# Test.net
KiCad netlist of a schematic drawn in EasyEDA Pro
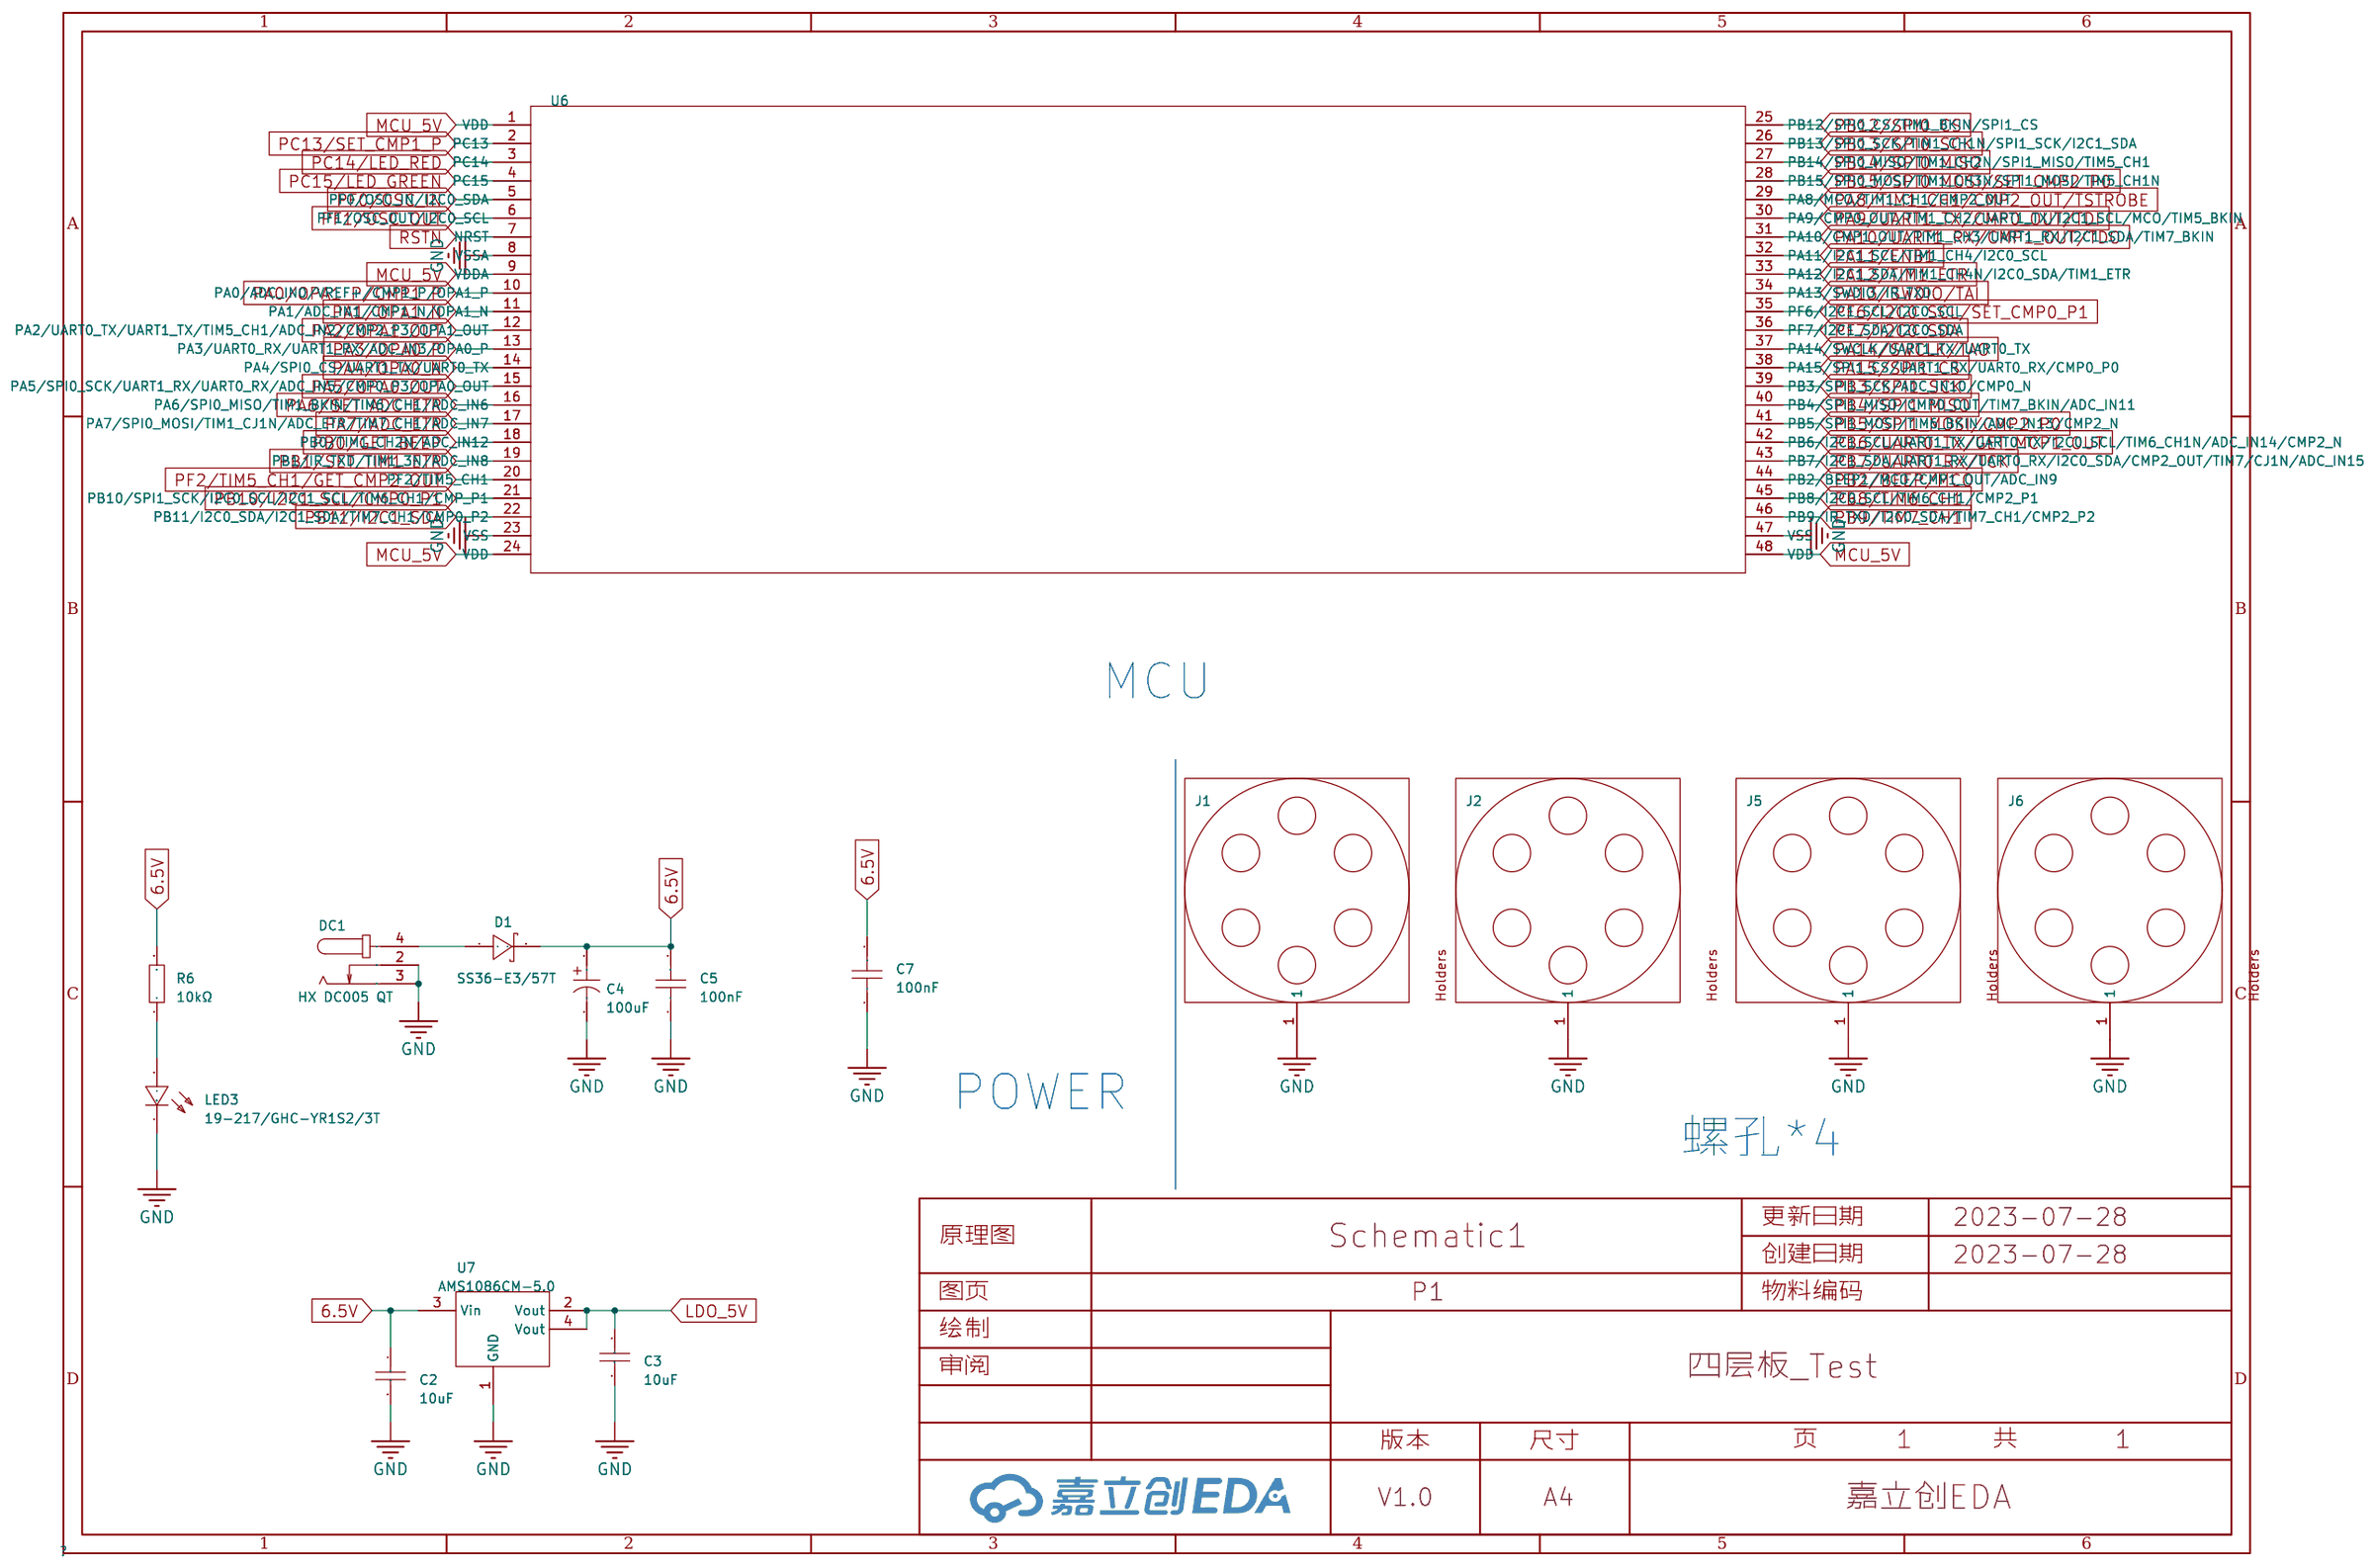
[diagram p0: schematic sheet]

(export (version "E")
  (design (tool "Eeschema 10.0.6"))
  (components
    (comp (ref "C2")
      (value "10uF")
      (footprint "easyedapro:C1206")
      (description "容值:10uF;精度:±10%;额定电压:50V;材质(温度系数):X5R;")
      (fields
        (field (name "Manufacturer Part") "CL31A106KBHNNNE")
        (field (name "Manufacturer") "SAMSUNG(三星)")
      )
      (libsource (lib "easyedapro") (part "CL31A106KBHNNNE"))
    )
    (comp (ref "C3")
      (value "10uF")
      (footprint "easyedapro:C1206")
      (description "容值:10uF;精度:±10%;额定电压:50V;材质(温度系数):X5R;")
      (fields
        (field (name "Manufacturer Part") "CL31A106KBHNNNE")
        (field (name "Manufacturer") "SAMSUNG(三星)")
      )
      (libsource (lib "easyedapro") (part "CL31A106KBHNNNE"))
    )
    (comp (ref "C4")
      (value "100uF")
      (footprint "easyedapro:CAP-SMD_BD6.3-L6.6-W6.6-LS7.6-FD-1")
      (description "容值:100uF;额定电压:35V;电容体直径:-;电容体长度:-;纹波电流:-;等效串联电阻:-;工作寿命:-;")
      (fields
        (field (name "Manufacturer Part") "RVE100UF35V67RV0072")
        (field (name "Manufacturer") "KNSCHA(科尼盛)")
      )
      (libsource (lib "easyedapro") (part "RVE100UF35V67RV0072"))
    )
    (comp (ref "C5")
      (value "100nF")
      (footprint "easyedapro:C0603")
      (description "容值:100nF;精度:±10%;额定电压:50V;材质(温度系数):X7R;")
      (fields
        (field (name "Manufacturer Part") "CL10B104KB8NNNC")
        (field (name "Manufacturer") "SAMSUNG(三星)")
      )
      (libsource (lib "easyedapro") (part "CL10B104KB8NNNC"))
    )
    (comp (ref "C7")
      (value "100nF")
      (footprint "easyedapro:C0603")
      (description "容值:100nF;精度:±10%;额定电压:50V;材质(温度系数):X7R;")
      (fields
        (field (name "Manufacturer Part") "CL10B104KB8NNNC")
        (field (name "Manufacturer") "SAMSUNG(三星)")
      )
      (libsource (lib "easyedapro") (part "CL10B104KB8NNNC"))
    )
    (comp (ref "D1")
      (value "SS36-E3/57T")
      (footprint "easyedapro:SMC_L7.1-W6.2-LS8.1-R-RD")
      (description "直流反向耐压（Vr）:60V;平均整流电流（Io）:3A;正向压降（Vf）:750mV @ 3A;")
      (fields (field (name "Manufacturer") "VISHAY(威世)"))
      (libsource (lib "easyedapro") (part "SS36-E3/57T"))
    )
    (comp (ref "DC1")
      (value "HX DC005 QT")
      (footprint "easyedapro:DC-IN-TH_HANXIA_HX-DC005-QT")
      (description "连接器类型:DC插座;安装方式:卧插;额定电流:1A;额定电压:12V;工作温度范围:-25°C~+85°C;")
      (fields (field (name "Manufacturer") "hanxia(韩下)"))
      (libsource (lib "easyedapro") (part "HX DC005 QT"))
    )
    (comp (ref "J1")
      (value "~")
      (footprint "easyedapro:DEMO板安装孔")
      (libsource (lib "easyedapro") (part "螺孔_3.1X6MM"))
    )
    (comp (ref "J2")
      (value "~")
      (footprint "easyedapro:DEMO板安装孔")
      (libsource (lib "easyedapro") (part "螺孔_3.1X6MM"))
    )
    (comp (ref "J5")
      (value "~")
      (footprint "easyedapro:DEMO板安装孔")
      (libsource (lib "easyedapro") (part "螺孔_3.1X6MM"))
    )
    (comp (ref "J6")
      (value "~")
      (footprint "easyedapro:DEMO板安装孔")
      (libsource (lib "easyedapro") (part "螺孔_3.1X6MM"))
    )
    (comp (ref "LED3")
      (value "19-217/GHC-YR1S2/3T")
      (footprint "easyedapro:LED0603-RD")
      (fields (field (name "Manufacturer") "EVERLIGHT(亿光)"))
      (libsource (lib "easyedapro") (part "19-217/GHC-YR1S2/3T"))
    )
    (comp (ref "R6")
      (value "10kΩ")
      (footprint "easyedapro:R0603")
      (description "电阻类型:厚膜电阻;阻值:10kΩ;精度:±1%;功率:100mW;温度系数:±100ppm/°C;最大工作电压:75V;工作温度范围:-55°C~+155°C;")
      (fields
        (field (name "Manufacturer Part") "0603WAF1002T5E")
        (field (name "Manufacturer") "UNI-ROYAL(厚声)")
      )
      (libsource (lib "easyedapro") (part "0603WAF1002T5E"))
    )
    (comp (ref "U6") (value "PT32A030C8T7") (libsource (lib "easyedapro") (part "PT32A030C8T7")))
    (comp (ref "U7")
      (value "AMS1086CM-5.0")
      (footprint "easyedapro:TO-263-3_L8.6-W10.2-P2.54-LS14.4-TL")
      (description "输出类型:固定;输出极性:正;最大输入电压:15V;输出电压:5V;输出电流:1.5A;电源纹波抑制比(PSRR):68dB@(120Hz);")
      (fields (field (name "Manufacturer") "AMS"))
      (libsource (lib "easyedapro") (part "AMS1086CM-5.0"))
    )
  )
  (nets
    (net (code "1") (name "6.5V") (class "Default")
      (node (ref "C2") (pin "1") (pinfunction "1_1") (pintype "input"))
      (node (ref "C4") (pin "1") (pinfunction "1_1") (pintype "input"))
      (node (ref "C5") (pin "2") (pinfunction "2_2") (pintype "input"))
      (node (ref "C7") (pin "2") (pinfunction "2_2") (pintype "input"))
      (node (ref "D1") (pin "2") (pinfunction "K_2") (pintype "input"))
      (node (ref "R6") (pin "2") (pinfunction "2_2") (pintype "input"))
      (node (ref "U7") (pin "3") (pinfunction "Vin_3") (pintype "input"))
    )
    (net (code "2") (name "GND") (class "Default")
      (node (ref "C2") (pin "2") (pinfunction "2_2") (pintype "input"))
      (node (ref "C3") (pin "1") (pinfunction "1_1") (pintype "input"))
      (node (ref "C4") (pin "2") (pinfunction "2_2") (pintype "input"))
      (node (ref "C5") (pin "1") (pinfunction "1_1") (pintype "input"))
      (node (ref "C7") (pin "1") (pinfunction "1_1") (pintype "input"))
      (node (ref "DC1") (pin "2") (pinfunction "2_2") (pintype "input"))
      (node (ref "DC1") (pin "3") (pinfunction "3_3") (pintype "input"))
      (node (ref "J1") (pin "1") (pinfunction "1_1") (pintype "input"))
      (node (ref "J2") (pin "1") (pinfunction "1_1") (pintype "input"))
      (node (ref "J5") (pin "1") (pinfunction "1_1") (pintype "input"))
      (node (ref "J6") (pin "1") (pinfunction "1_1") (pintype "input"))
      (node (ref "LED3") (pin "1") (pinfunction "C_1") (pintype "input"))
      (node (ref "U6") (pin "23") (pinfunction "VSS_23") (pintype "input"))
      (node (ref "U6") (pin "47") (pinfunction "VSS_47") (pintype "input"))
      (node (ref "U6") (pin "8") (pinfunction "VSSA_8") (pintype "input"))
      (node (ref "U7") (pin "1") (pinfunction "GND_1") (pintype "input"))
    )
    (net (code "3") (name "LDO_5V") (class "Default")
      (node (ref "C3") (pin "2") (pinfunction "2_2") (pintype "input"))
      (node (ref "U7") (pin "2") (pinfunction "Vout_2") (pintype "input"))
      (node (ref "U7") (pin "4") (pinfunction "Vout_4") (pintype "input"))
    )
    (net (code "4") (name "MCU_5V") (class "Default")
      (node (ref "U6") (pin "1") (pinfunction "VDD_1") (pintype "input"))
      (node (ref "U6") (pin "24") (pinfunction "VDD_24") (pintype "input"))
      (node (ref "U6") (pin "48") (pinfunction "VDD_48") (pintype "input"))
      (node (ref "U6") (pin "9") (pinfunction "VDDA_9") (pintype "input"))
    )
    (net (code "5") (name "Net-(D1-A)") (class "Default")
      (node (ref "D1") (pin "1") (pinfunction "A_1") (pintype "input"))
      (node (ref "DC1") (pin "4") (pinfunction "4_4") (pintype "input"))
    )
    (net (code "6") (name "Net-(LED3-A)") (class "Default")
      (node (ref "LED3") (pin "2") (pinfunction "A_2") (pintype "input"))
      (node (ref "R6") (pin "1") (pinfunction "1_1") (pintype "input"))
    )
    (net (code "7") (name "PA0{slash}OPA1_P{slash}CMP1_P") (class "Default")
      (node (ref "U6") (pin "10") (pinfunction "PA0/ADC_IN0/VREF+/CMP1_P/OPA1_P_10") (pintype "input"))
    )
    (net (code "8") (name "PA1{slash}OPA1_N") (class "Default")
      (node (ref "U6") (pin "11") (pinfunction "PA1/ADC_IN1/CMP1_N/OPA1_N_11") (pintype "input"))
    )
    (net (code "9") (name "PA2{slash}OPA1_OUT") (class "Default")
      (node (ref "U6") (pin "12") (pinfunction "PA2/UART0_TX/UART1_TX/TIM5_CH1/ADC_IN2/CMP2_P3/OPA1_OUT_12") (pintype "input"))
    )
    (net (code "10") (name "PA3{slash}OPA0_P") (class "Default")
      (node (ref "U6") (pin "13") (pinfunction "PA3/UART0_RX/UART1_RX/ADC_IN3/OPA0_P_13") (pintype "input"))
    )
    (net (code "11") (name "PA4{slash}OPA0_N") (class "Default")
      (node (ref "U6") (pin "14") (pinfunction "PA4/SPI0_CS/UART1_TX/UART0_TX_14") (pintype "input"))
    )
    (net (code "12") (name "PA5{slash}OPA0_OUT") (class "Default")
      (node (ref "U6") (pin "15") (pinfunction "PA5/SPI0_SCK/UART1_RX/UART0_RX/ADC_IN5/CMP0_P3/OPA0_OUT_15") (pintype "input"))
    )
    (net (code "13") (name "PA6{slash}SET_ADC_ETR") (class "Default")
      (node (ref "U6") (pin "16") (pinfunction "PA6/SPI0_MISO/TIM1_BKIN/TIM6/CH1/ADC_IN6_16") (pintype "input"))
    )
    (net (code "14") (name "PA7{slash}ADC_ETR") (class "Default")
      (node (ref "U6") (pin "17") (pinfunction "PA7/SPI0_MOSI/TIM1_CJ1N/ADC_ETR/TIM7_CH1/ADC_IN7_17") (pintype "input"))
    )
    (net (code "15") (name "PA8{slash}TIM1_CH1{slash}CMP2_OUT{slash}TSTROBE") (class "Default")
      (node (ref "U6") (pin "29") (pinfunction "PA8/MCO/TIM1_CH1/CMP2_OUT_29") (pintype "input"))
    )
    (net (code "16") (name "PA9{slash}UART1_TX{slash}CMP0_OUT{slash}TDI") (class "Default")
      (node (ref "U6") (pin "30") (pinfunction "PA9/CMP0_OUT/TIM1_CH2/UART1_TX/I2C1_SCL/MCO/TIM5_BKIN_30") (pintype "input"))
    )
    (net (code "17") (name "PA10{slash}UART1_RX{slash}CMP1_OUT{slash}TDO") (class "Default")
      (node (ref "U6") (pin "31") (pinfunction "PA10/CMP1_OUT/TIM1_CH3/UART1_RX/I2C1_SDA/TIM7_BKIN_31") (pintype "input"))
    )
    (net (code "18") (name "PA11{slash}ENB1") (class "Default")
      (node (ref "U6") (pin "32") (pinfunction "PA11/I2C1_SCL/TIM1_CH4/I2C0_SCL_32") (pintype "input"))
    )
    (net (code "19") (name "PA12{slash}TIM1_ETR") (class "Default")
      (node (ref "U6") (pin "33") (pinfunction "PA12/I2C1_SDA/TIM1_CH4N/I2C0_SDA/TIM1_ETR_33") (pintype "input"))
    )
    (net (code "20") (name "PA13{slash}SWDIO{slash}TAI") (class "Default")
      (node (ref "U6") (pin "34") (pinfunction "PA13/SWDIO/IR_TXD_34") (pintype "input"))
    )
    (net (code "21") (name "PA14{slash}SWCLK{slash}TAO") (class "Default")
      (node (ref "U6") (pin "37") (pinfunction "PA14/SWCLK/UART1_TX/UART0_TX_37") (pintype "input"))
    )
    (net (code "22") (name "PA15{slash}SPI1_CS") (class "Default")
      (node (ref "U6") (pin "38") (pinfunction "PA15/SPI1_CS/UART1_RX/UART0_RX/CMP0_P0_38") (pintype "input"))
    )
    (net (code "23") (name "PB0{slash}GET_BEEP") (class "Default")
      (node (ref "U6") (pin "18") (pinfunction "PB0/TIM1_CH2N/ADC_IN12_18") (pintype "input"))
    )
    (net (code "24") (name "PB1{slash}SET_TIM1_ETR") (class "Default")
      (node (ref "U6") (pin "19") (pinfunction "PB1/IR_TXD/TIM1_3N/ADC_IN8_19") (pintype "input"))
    )
    (net (code "25") (name "PB2{slash}BEEP{slash}MCO") (class "Default")
      (node (ref "U6") (pin "44") (pinfunction "PB2/BEEP1/MCO/CMP1_OUT/ADC_IN9_44") (pintype "input"))
    )
    (net (code "26") (name "PB3{slash}SPI1_SCK") (class "Default")
      (node (ref "U6") (pin "39") (pinfunction "PB3/SPI1_SCK/ADC_IN10/CMP0_N_39") (pintype "input"))
    )
    (net (code "27") (name "PB4{slash}SPI1_MISO") (class "Default")
      (node (ref "U6") (pin "40") (pinfunction "PB4/SPI1_MISO/CMP0_OUT/TIM7_BKIN/ADC_IN11_40") (pintype "input"))
    )
    (net (code "28") (name "PB5{slash}SPI1_MOSI{slash}CMP2_P0") (class "Default")
      (node (ref "U6") (pin "41") (pinfunction "PB5/SPI1_MOSI/TIM6_BKIN/ADC_IN13/CMP2_N_41") (pintype "input"))
    )
    (net (code "29") (name "PB6{slash}UART0_TX{slash}GET_MCP1_OUT") (class "Default")
      (node (ref "U6") (pin "42") (pinfunction "PB6/I2C1_SCL/UART1_TX/UART0_TX/I2C0_SCL/TIM6_CH1N/ADC_IN14/CMP2_N_42") (pintype "input"))
    )
    (net (code "30") (name "PB7{slash}UART0_RX{slash}TCK") (class "Default")
      (node (ref "U6") (pin "43") (pinfunction "PB7/I2C1_SDA/UART1_RX/UART0_RX/I2C0_SDA/CMP2_OUT/TIM7/CJ1N/ADC_IN15_43") (pintype "input"))
    )
    (net (code "31") (name "PB8{slash}TIM6_CH1") (class "Default")
      (node (ref "U6") (pin "45") (pinfunction "PB8/I2C0_SCL/TIM6_CH1/CMP2_P1_45") (pintype "input"))
    )
    (net (code "32") (name "PB9{slash}TIM7_CH1") (class "Default")
      (node (ref "U6") (pin "46") (pinfunction "PB9/IR_TXD/I2C0_SDA/TIM7_CH1/CMP2_P2_46") (pintype "input"))
    )
    (net (code "33") (name "PB10{slash}I2C1_SCL{slash}CMP0_P1") (class "Default")
      (node (ref "U6") (pin "21") (pinfunction "PB10/SPI1_SCK/I2C0_SCL/I2C1_SCL/TIM6_CH1/CMP_P1_21") (pintype "input"))
    )
    (net (code "34") (name "PB11{slash}I2C1_SDA") (class "Default")
      (node (ref "U6") (pin "22") (pinfunction "PB11/I2C0_SDA/I2C1_SDA/TIM7_CH1/CMP0_P2_22") (pintype "input"))
    )
    (net (code "35") (name "PB12{slash}SPI0_CS") (class "Default")
      (node (ref "U6") (pin "25") (pinfunction "PB12/SPI0_CS/TIM1_BKIN/SPI1_CS_25") (pintype "input"))
    )
    (net (code "36") (name "PB13{slash}SPI0_SCK") (class "Default")
      (node (ref "U6") (pin "26") (pinfunction "PB13/SPI0_SCK/TIM1_CH1N/SPI1_SCK/I2C1_SDA_26") (pintype "input"))
    )
    (net (code "37") (name "PB14{slash}SPI0_MISO") (class "Default")
      (node (ref "U6") (pin "27") (pinfunction "PB14/SPI0_MISO/TIM1_CH2N/SPI1_MISO/TIM5_CH1_27") (pintype "input"))
    )
    (net (code "38") (name "PB15{slash}SPI0_MOSI{slash}SET_CMP2_P0") (class "Default")
      (node (ref "U6") (pin "28") (pinfunction "PB15/SPI0_MOSI/TIM1_CH3N/SPI1_MOSI/TIM5_CH1N_28") (pintype "input"))
    )
    (net (code "39") (name "PC13{slash}SET_CMP1_P") (class "Default")
      (node (ref "U6") (pin "2") (pinfunction "PC13_2") (pintype "input"))
    )
    (net (code "40") (name "PC14{slash}LED_RED") (class "Default")
      (node (ref "U6") (pin "3") (pinfunction "PC14_3") (pintype "input"))
    )
    (net (code "41") (name "PC15{slash}LED_GREEN") (class "Default")
      (node (ref "U6") (pin "4") (pinfunction "PC15_4") (pintype "input"))
    )
    (net (code "42") (name "PF0{slash}OSC_IN") (class "Default")
      (node (ref "U6") (pin "5") (pinfunction "PF0/OSC_IN/I2C0_SDA_5") (pintype "input"))
    )
    (net (code "43") (name "PF1{slash}OSC_OUT") (class "Default")
      (node (ref "U6") (pin "6") (pinfunction "PF1/OSC_OUT/I2C0_SCL_6") (pintype "input"))
    )
    (net (code "44") (name "PF2{slash}TIM5_CH1{slash}GET_CMP2_OUT") (class "Default")
      (node (ref "U6") (pin "20") (pinfunction "PF2/TIM5_CH1_20") (pintype "input"))
    )
    (net (code "45") (name "PF6{slash}I2C0_SCL{slash}SET_CMP0_P1") (class "Default")
      (node (ref "U6") (pin "35") (pinfunction "PF6/I2C1_SCL/I2C0_SCL_35") (pintype "input"))
    )
    (net (code "46") (name "PF7{slash}I2C0_SDA") (class "Default")
      (node (ref "U6") (pin "36") (pinfunction "PF7/I2C1_SDA/I2C0_SDA_36") (pintype "input"))
    )
    (net (code "47") (name "RSTN") (class "Default")
      (node (ref "U6") (pin "7") (pinfunction "NRST_7") (pintype "input"))
    )
  )
)
